# cover.net
KiCad netlist of a schematic drawn in Altium Designer
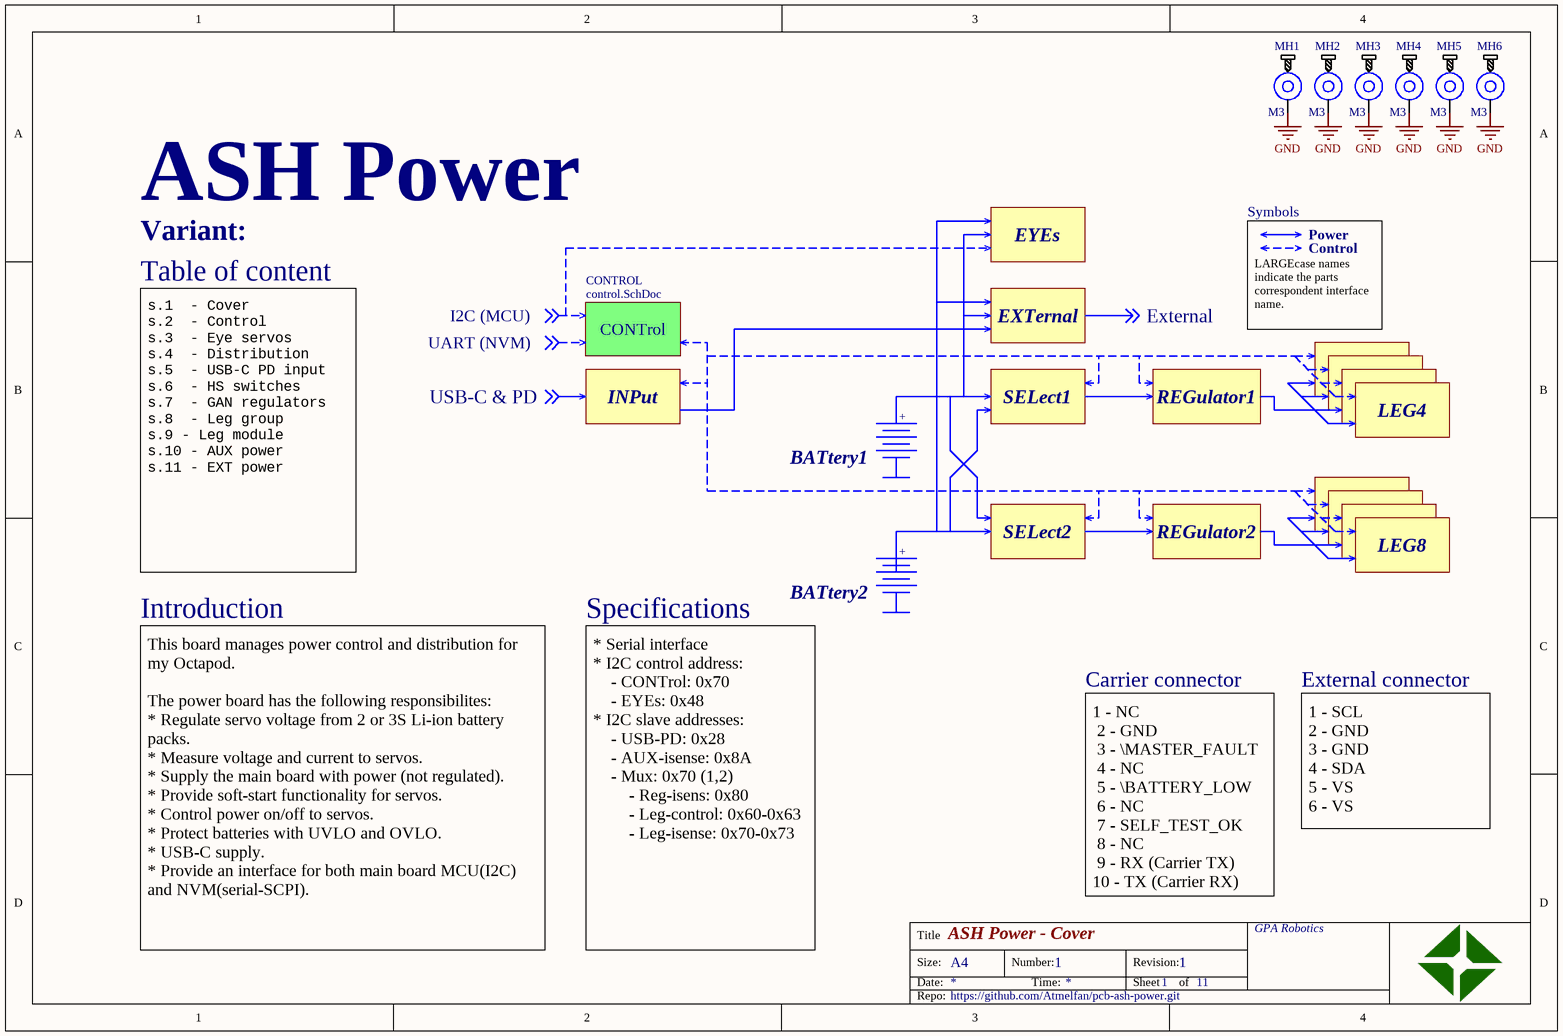
[diagram p0: cover.SchDoc]

(export (version "E")
  (design (tool "Eeschema 10.0.6"))
  (components
    (comp (ref "MH1")
      (value "M3")
      (footprint "mount_m3_normal")
      (description "Mounting hole")
      (libsource (lib "lib_mechanical") (part "mounting_hole"))
    )
    (comp (ref "MH2")
      (value "M3")
      (footprint "mount_m3_normal")
      (description "Mounting hole")
      (libsource (lib "lib_mechanical") (part "mounting_hole"))
    )
    (comp (ref "MH3")
      (value "M3")
      (footprint "mount_m3_normal")
      (description "Mounting hole")
      (libsource (lib "lib_mechanical") (part "mounting_hole"))
    )
    (comp (ref "MH4")
      (value "M3")
      (footprint "mount_m3_normal")
      (description "Mounting hole")
      (libsource (lib "lib_mechanical") (part "mounting_hole"))
    )
    (comp (ref "MH5")
      (value "M3")
      (footprint "mount_m3_normal")
      (description "Mounting hole")
      (libsource (lib "lib_mechanical") (part "mounting_hole"))
    )
    (comp (ref "MH6")
      (value "M3")
      (footprint "mount_m3_normal")
      (description "Mounting hole")
      (libsource (lib "lib_mechanical") (part "mounting_hole"))
    )
  )
  (nets
    (net (code "1") (name "GND") (class "Default")
      (node (ref "MH1") (pin "1") (pinfunction "1_1") (pintype "passive"))
      (node (ref "MH2") (pin "1") (pinfunction "1_1") (pintype "passive"))
      (node (ref "MH3") (pin "1") (pinfunction "1_1") (pintype "passive"))
      (node (ref "MH4") (pin "1") (pinfunction "1_1") (pintype "passive"))
      (node (ref "MH5") (pin "1") (pinfunction "1_1") (pintype "passive"))
      (node (ref "MH6") (pin "1") (pinfunction "1_1") (pintype "passive"))
    )
  )
)
